# Input_Schematic.net
KiCad netlist of a schematic drawn in Altium Designer
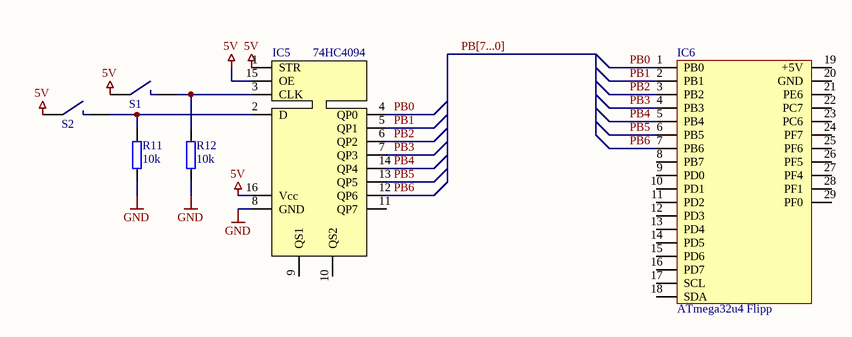
[diagram p0: Input_Schematic.SchDoc]

(export (version "E")
  (design (tool "Eeschema 10.0.6"))
  (components
    (comp (ref "IC5")
      (value "74HC4094")
      (description "Serial Input, Serial and Parallel Output; 8 Bit")
      (libsource (lib "Staudi_Lib") (part "74HC4094"))
    )
    (comp (ref "IC6") (value "ATmega32u4 Flipp") (libsource (lib "Staudi_Lib") (part "Flipp")))
    (comp (ref "R11") (value "10k") (footprint "Axial-04") (libsource (lib "Staudi_Lib") (part "Res")))
    (comp (ref "R12") (value "10k") (footprint "Axial-04") (libsource (lib "Staudi_Lib") (part "Res")))
    (comp (ref "S1") (value "Switch") (libsource (lib "Staudi_Lib") (part "Switch")))
    (comp (ref "S2") (value "Switch") (libsource (lib "Staudi_Lib") (part "Switch")))
  )
  (nets
    (net (code "2") (name "/PB0") (class "Default")
      (node (ref "IC5") (pin "4") (pinfunction "QP0_4") (pintype "passive"))
      (node (ref "IC6") (pin "1") (pinfunction "PB0_1") (pintype "passive"))
    )
    (net (code "3") (name "/PB1") (class "Default")
      (node (ref "IC5") (pin "5") (pinfunction "QP1_5") (pintype "passive"))
      (node (ref "IC6") (pin "2") (pinfunction "PB1_2") (pintype "passive"))
    )
    (net (code "4") (name "/PB2") (class "Default")
      (node (ref "IC5") (pin "6") (pinfunction "QP2_6") (pintype "passive"))
      (node (ref "IC6") (pin "3") (pinfunction "PB2_3") (pintype "passive"))
    )
    (net (code "5") (name "/PB3") (class "Default")
      (node (ref "IC5") (pin "7") (pinfunction "QP3_7") (pintype "passive"))
      (node (ref "IC6") (pin "4") (pinfunction "PB3_4") (pintype "passive"))
    )
    (net (code "6") (name "/PB4") (class "Default")
      (node (ref "IC5") (pin "14") (pinfunction "QP4_14") (pintype "passive"))
      (node (ref "IC6") (pin "5") (pinfunction "PB4_5") (pintype "passive"))
    )
    (net (code "7") (name "/PB5") (class "Default")
      (node (ref "IC5") (pin "13") (pinfunction "QP5_13") (pintype "passive"))
      (node (ref "IC6") (pin "6") (pinfunction "PB5_6") (pintype "passive"))
    )
    (net (code "8") (name "/PB6") (class "Default")
      (node (ref "IC5") (pin "12") (pinfunction "QP6_12") (pintype "passive"))
      (node (ref "IC6") (pin "7") (pinfunction "PB6_7") (pintype "passive"))
    )
    (net (code "10") (name "5V") (class "Default")
      (node (ref "IC5") (pin "1") (pinfunction "STR_1") (pintype "passive"))
      (node (ref "IC5") (pin "15") (pinfunction "OE_15") (pintype "passive"))
      (node (ref "IC5") (pin "16") (pinfunction "Vcc_16") (pintype "passive"))
      (node (ref "S1") (pin "1") (pinfunction "1_1") (pintype "passive"))
      (node (ref "S2") (pin "1") (pinfunction "1_1") (pintype "passive"))
    )
    (net (code "11") (name "GND") (class "Default")
      (node (ref "IC5") (pin "8") (pinfunction "GND_8") (pintype "passive"))
      (node (ref "R11") (pin "1") (pinfunction "1_1") (pintype "passive"))
      (node (ref "R12") (pin "1") (pinfunction "1_1") (pintype "passive"))
    )
    (net (code "12") (name "Net-(IC5-CLK)") (class "Default")
      (node (ref "IC5") (pin "3") (pinfunction "CLK_3") (pintype "passive"))
      (node (ref "R12") (pin "2") (pinfunction "2_2") (pintype "passive"))
      (node (ref "S1") (pin "2") (pinfunction "2_2") (pintype "passive"))
    )
    (net (code "13") (name "Net-(IC5-D)") (class "Default")
      (node (ref "IC5") (pin "2") (pinfunction "D_2") (pintype "passive"))
      (node (ref "R11") (pin "2") (pinfunction "2_2") (pintype "passive"))
      (node (ref "S2") (pin "2") (pinfunction "2_2") (pintype "passive"))
    )
    (net (code "14") (name "unconnected-(IC5-QP7-Pad11)") (class "Default")
      (node (ref "IC5") (pin "11") (pinfunction "QP7_11") (pintype "passive"))
    )
    (net (code "15") (name "unconnected-(IC5-QS1-Pad9)") (class "Default")
      (node (ref "IC5") (pin "9") (pinfunction "QS1_9") (pintype "passive"))
    )
    (net (code "16") (name "unconnected-(IC5-QS2-Pad10)") (class "Default")
      (node (ref "IC5") (pin "10") (pinfunction "QS2_10") (pintype "passive"))
    )
    (net (code "17") (name "unconnected-(IC6-+5V-Pad19)") (class "Default")
      (node (ref "IC6") (pin "19") (pinfunction "+5V_19") (pintype "passive"))
    )
    (net (code "18") (name "unconnected-(IC6-GND-Pad20)") (class "Default")
      (node (ref "IC6") (pin "20") (pinfunction "GND_20") (pintype "passive"))
    )
    (net (code "19") (name "unconnected-(IC6-PB7-Pad8)") (class "Default")
      (node (ref "IC6") (pin "8") (pinfunction "PB7_8") (pintype "passive"))
    )
    (net (code "20") (name "unconnected-(IC6-PC6-Pad23)") (class "Default")
      (node (ref "IC6") (pin "23") (pinfunction "PC6_23") (pintype "passive"))
    )
    (net (code "21") (name "unconnected-(IC6-PC7-Pad22)") (class "Default")
      (node (ref "IC6") (pin "22") (pinfunction "PC7_22") (pintype "passive"))
    )
    (net (code "22") (name "unconnected-(IC6-PD0-Pad9)") (class "Default")
      (node (ref "IC6") (pin "9") (pinfunction "PD0_9") (pintype "passive"))
    )
    (net (code "23") (name "unconnected-(IC6-PD1-Pad10)") (class "Default")
      (node (ref "IC6") (pin "10") (pinfunction "PD1_10") (pintype "passive"))
    )
    (net (code "24") (name "unconnected-(IC6-PD2-Pad11)") (class "Default")
      (node (ref "IC6") (pin "11") (pinfunction "PD2_11") (pintype "passive"))
    )
    (net (code "25") (name "unconnected-(IC6-PD3-Pad12)") (class "Default")
      (node (ref "IC6") (pin "12") (pinfunction "PD3_12") (pintype "passive"))
    )
    (net (code "26") (name "unconnected-(IC6-PD4-Pad13)") (class "Default")
      (node (ref "IC6") (pin "13") (pinfunction "PD4_13") (pintype "passive"))
    )
    (net (code "27") (name "unconnected-(IC6-PD5-Pad14)") (class "Default")
      (node (ref "IC6") (pin "14") (pinfunction "PD5_14") (pintype "passive"))
    )
    (net (code "28") (name "unconnected-(IC6-PD6-Pad15)") (class "Default")
      (node (ref "IC6") (pin "15") (pinfunction "PD6_15") (pintype "passive"))
    )
    (net (code "29") (name "unconnected-(IC6-PD7-Pad16)") (class "Default")
      (node (ref "IC6") (pin "16") (pinfunction "PD7_16") (pintype "passive"))
    )
    (net (code "30") (name "unconnected-(IC6-PE6-Pad21)") (class "Default")
      (node (ref "IC6") (pin "21") (pinfunction "PE6_21") (pintype "passive"))
    )
    (net (code "31") (name "unconnected-(IC6-PF0-Pad29)") (class "Default")
      (node (ref "IC6") (pin "29") (pinfunction "PF0_29") (pintype "passive"))
    )
    (net (code "32") (name "unconnected-(IC6-PF1-Pad28)") (class "Default")
      (node (ref "IC6") (pin "28") (pinfunction "PF1_28") (pintype "passive"))
    )
    (net (code "33") (name "unconnected-(IC6-PF4-Pad27)") (class "Default")
      (node (ref "IC6") (pin "27") (pinfunction "PF4_27") (pintype "passive"))
    )
    (net (code "34") (name "unconnected-(IC6-PF5-Pad26)") (class "Default")
      (node (ref "IC6") (pin "26") (pinfunction "PF5_26") (pintype "passive"))
    )
    (net (code "35") (name "unconnected-(IC6-PF6-Pad25)") (class "Default")
      (node (ref "IC6") (pin "25") (pinfunction "PF6_25") (pintype "passive"))
    )
    (net (code "36") (name "unconnected-(IC6-PF7-Pad24)") (class "Default")
      (node (ref "IC6") (pin "24") (pinfunction "PF7_24") (pintype "passive"))
    )
    (net (code "37") (name "unconnected-(IC6-SCL-Pad17)") (class "Default")
      (node (ref "IC6") (pin "17") (pinfunction "SCL_17") (pintype "passive"))
    )
    (net (code "38") (name "unconnected-(IC6-SDA-Pad18)") (class "Default")
      (node (ref "IC6") (pin "18") (pinfunction "SDA_18") (pintype "passive"))
    )
  )
)
